# ManitoBoardL3.net
KiCad netlist of a schematic drawn in EAGLE
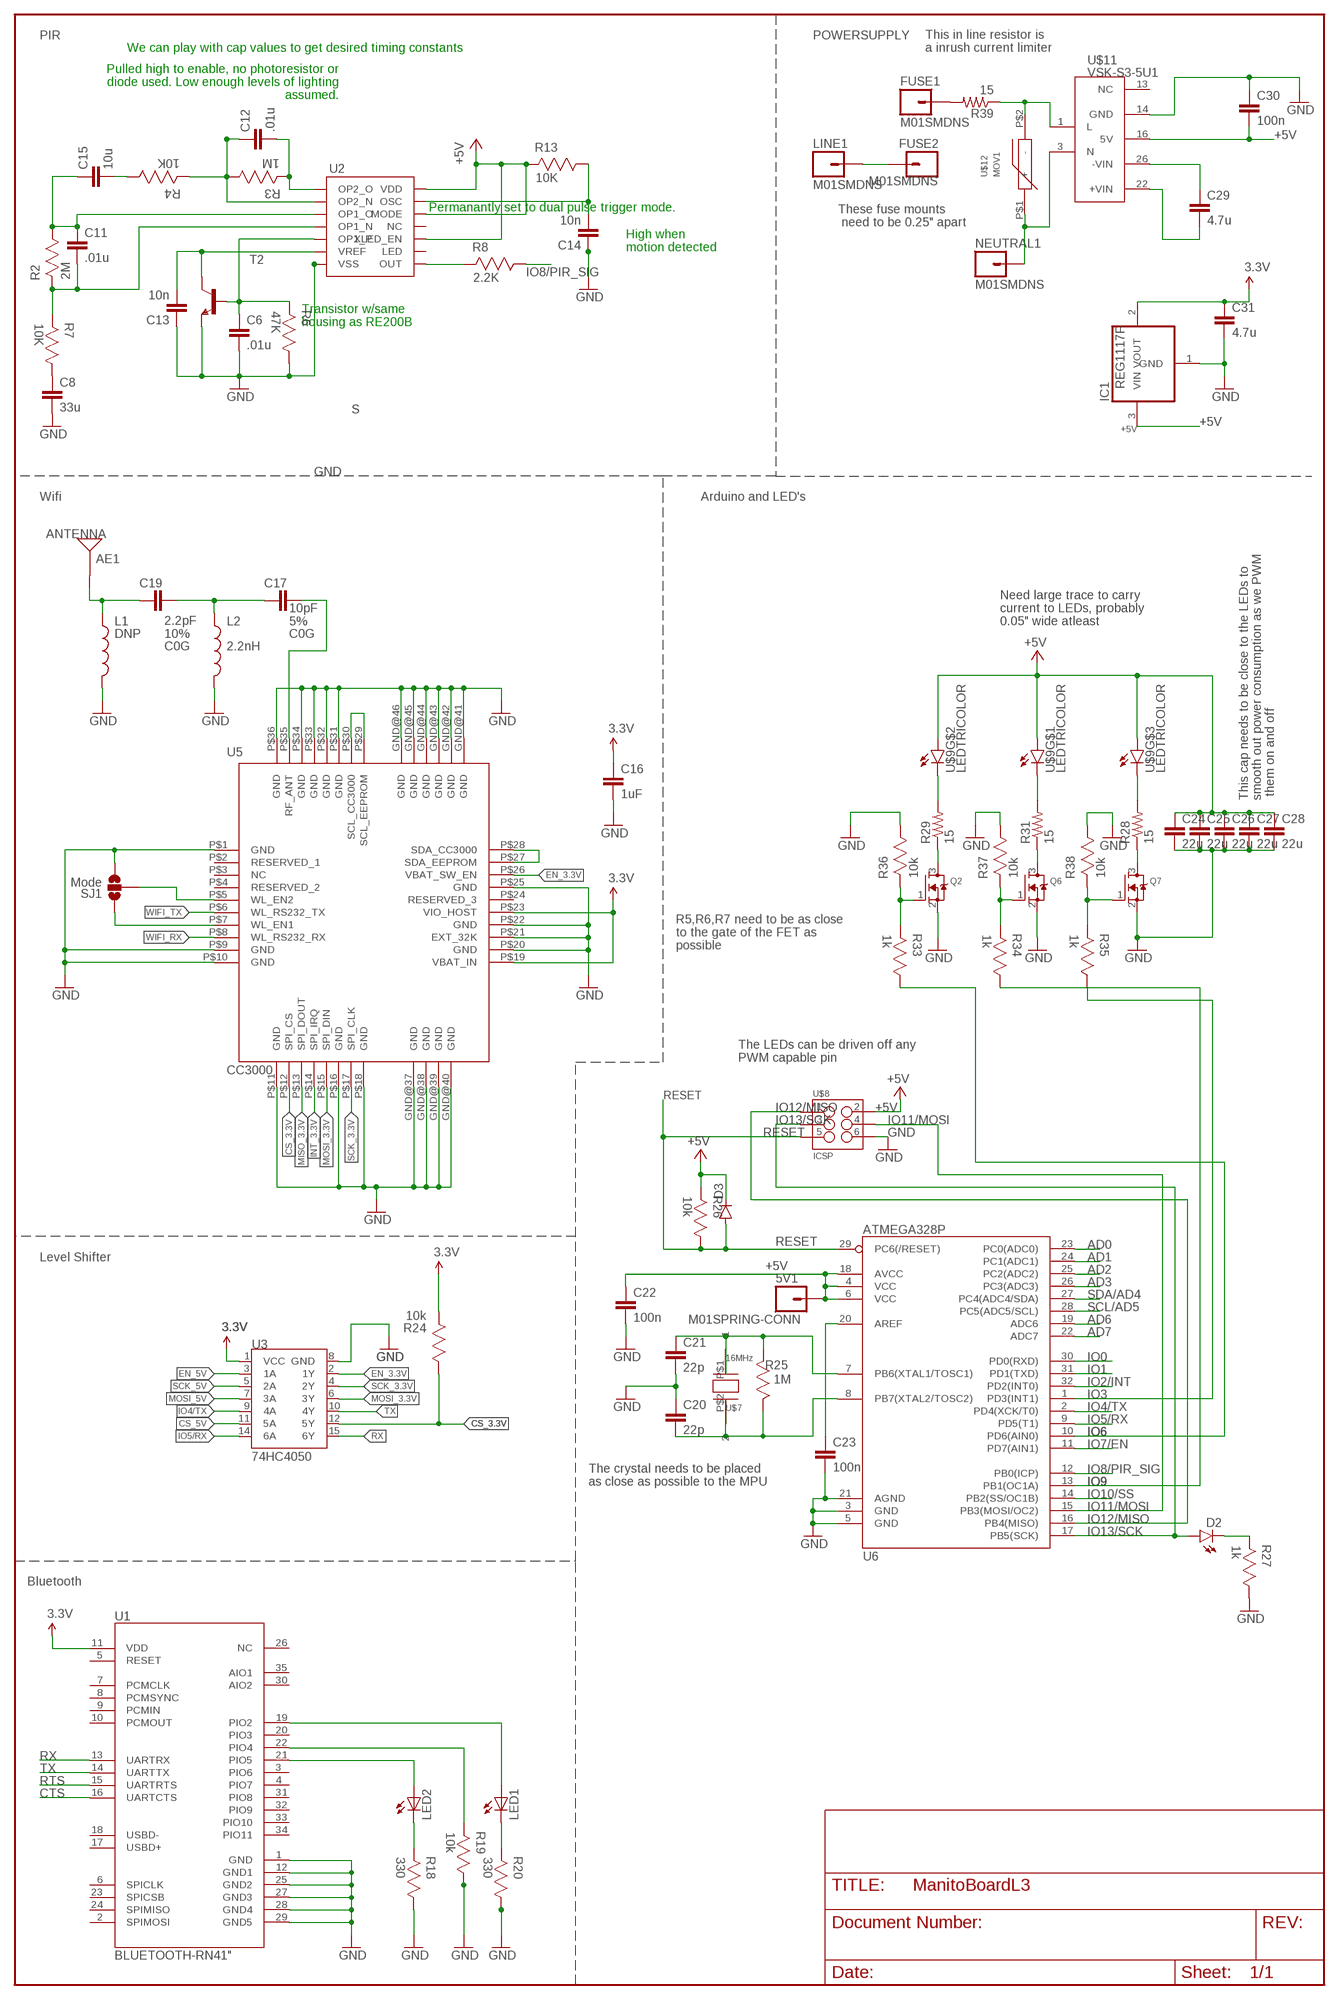
[diagram p0: schematic, sheet 1]

(export (version "E")
  (design (tool "Eeschema 10.0.6"))
  (components
    (comp (ref "5V1")
      (value "M01SPRING-CONN")
      (footprint "eagle-import:SPRING-CONNECTOR")
      (libsource (lib "eagle-import") (part "M01SPRING-CONN"))
    )
    (comp (ref "AE1")
      (value "ANTENNA")
      (footprint "eagle-import:ANTENNA-CHIP_2500AT44M0400")
      (libsource (lib "eagle-import") (part "ANTENNA22500AT44M0400"))
    )
    (comp (ref "C6")
      (value ".01u")
      (footprint "eagle-import:0805")
      (libsource (lib "eagle-import") (part "CAP0805"))
    )
    (comp (ref "C8")
      (value "33u")
      (footprint "eagle-import:0805")
      (libsource (lib "eagle-import") (part "CAP0805"))
    )
    (comp (ref "C11")
      (value ".01u")
      (footprint "eagle-import:0805")
      (libsource (lib "eagle-import") (part "CAP0805"))
    )
    (comp (ref "C12")
      (value ".01u")
      (footprint "eagle-import:0805")
      (libsource (lib "eagle-import") (part "CAP0805"))
    )
    (comp (ref "C13")
      (value "10n")
      (footprint "eagle-import:0805")
      (libsource (lib "eagle-import") (part "CAP0805"))
    )
    (comp (ref "C14")
      (value "10n")
      (footprint "eagle-import:0805")
      (libsource (lib "eagle-import") (part "CAP0805"))
    )
    (comp (ref "C15")
      (value "10u")
      (footprint "eagle-import:0805")
      (libsource (lib "eagle-import") (part "CAP0805"))
    )
    (comp (ref "C16")
      (value "1uF")
      (footprint "eagle-import:0805")
      (libsource (lib "eagle-import") (part "SparkFun-Capacitors_CAP0805"))
    )
    (comp (ref "C17")
      (value "10pF")
      (footprint "eagle-import:0603-CAP")
      (fields (field (name "COEFF") "C0G") (field (name "TOL") "5%"))
      (libsource (lib "eagle-import") (part "SparkFun-Capacitors_CAP0603-CAP"))
    )
    (comp (ref "C19")
      (value "2.2pF")
      (footprint "eagle-import:0603-CAP")
      (fields (field (name "COEFF") "C0G") (field (name "TOL") "10%"))
      (libsource (lib "eagle-import") (part "SparkFun-Capacitors_CAP0603-CAP"))
    )
    (comp (ref "C20")
      (value "22p")
      (footprint "eagle-import:0603-CAP")
      (libsource (lib "eagle-import") (part "CAP0603-CAP"))
    )
    (comp (ref "C21")
      (value "22p")
      (footprint "eagle-import:0603-CAP")
      (libsource (lib "eagle-import") (part "CAP0603-CAP"))
    )
    (comp (ref "C22")
      (value "100n")
      (footprint "eagle-import:0603-CAP")
      (libsource (lib "eagle-import") (part "CAP0603-CAP"))
    )
    (comp (ref "C23")
      (value "100n")
      (footprint "eagle-import:0603-CAP")
      (libsource (lib "eagle-import") (part "CAP0603-CAP"))
    )
    (comp (ref "C24")
      (value "22u")
      (footprint "eagle-import:0603-CAP")
      (libsource (lib "eagle-import") (part "CAP0603-CAP"))
    )
    (comp (ref "C25")
      (value "22u")
      (footprint "eagle-import:0603-CAP")
      (libsource (lib "eagle-import") (part "CAP0603-CAP"))
    )
    (comp (ref "C26")
      (value "22u")
      (footprint "eagle-import:0603-CAP")
      (libsource (lib "eagle-import") (part "CAP0603-CAP"))
    )
    (comp (ref "C27")
      (value "22u")
      (footprint "eagle-import:0603-CAP")
      (libsource (lib "eagle-import") (part "CAP0603-CAP"))
    )
    (comp (ref "C28")
      (value "22u")
      (footprint "eagle-import:0603-CAP")
      (libsource (lib "eagle-import") (part "CAP0603-CAP"))
    )
    (comp (ref "C29")
      (value "4.7u")
      (footprint "eagle-import:AXIAL-5MM")
      (libsource (lib "eagle-import") (part "CAP_"))
    )
    (comp (ref "C30")
      (value "100n")
      (footprint "eagle-import:0603-CAP")
      (libsource (lib "eagle-import") (part "CAP0603-CAP"))
    )
    (comp (ref "C31")
      (value "4.7u")
      (footprint "eagle-import:0603-CAP")
      (libsource (lib "eagle-import") (part "CAP0603-CAP"))
    )
    (comp (ref "D2")
      (value "LED-YELLOW0603")
      (footprint "eagle-import:LED-0603")
      (libsource (lib "eagle-import") (part "LED-YELLOW0603"))
    )
    (comp (ref "D3")
      (value "DIODESOD123")
      (footprint "eagle-import:SOD-123")
      (libsource (lib "eagle-import") (part "DIODESOD123"))
    )
    (comp (ref "FUSE1")
      (value "M01SMDNS")
      (footprint "eagle-import:1X01NS")
      (libsource (lib "eagle-import") (part "M01SMDNS"))
    )
    (comp (ref "FUSE2")
      (value "M01SMDNS")
      (footprint "eagle-import:1X01NS")
      (libsource (lib "eagle-import") (part "M01SMDNS"))
    )
    (comp (ref "IC1")
      (value "REG1117F")
      (footprint "eagle-import:DD-3")
      (fields (field (name "MF") "TEXAS INSTRUMENTS") (field (name "MPN") "REG1117FAKTTT"))
      (libsource (lib "eagle-import") (part "REG1117F"))
    )
    (comp (ref "L1")
      (value "DNP")
      (footprint "eagle-import:0603")
      (libsource (lib "eagle-import") (part "INDUCTOR0603"))
    )
    (comp (ref "L2")
      (value "2.2nH")
      (footprint "eagle-import:0603")
      (libsource (lib "eagle-import") (part "INDUCTOR0603"))
    )
    (comp (ref "LED1")
      (value "LED_ESML0603")
      (footprint "eagle-import:LED_SML0603")
      (libsource (lib "eagle-import") (part "LED_ESML0603"))
    )
    (comp (ref "LED2")
      (value "LED_ESML0603")
      (footprint "eagle-import:LED_SML0603")
      (libsource (lib "eagle-import") (part "LED_ESML0603"))
    )
    (comp (ref "LINE1")
      (value "M01SMDNS")
      (footprint "eagle-import:1X01NS")
      (libsource (lib "eagle-import") (part "M01SMDNS"))
    )
    (comp (ref "NEUTRAL1")
      (value "M01SMDNS")
      (footprint "eagle-import:1X01NS")
      (libsource (lib "eagle-import") (part "M01SMDNS"))
    )
    (comp (ref "Q2")
      (value "MOSFET-NREFLOW")
      (footprint "eagle-import:SOT23")
      (libsource (lib "eagle-import") (part "MOSFET-NREFLOW"))
    )
    (comp (ref "Q6")
      (value "MOSFET-NREFLOW")
      (footprint "eagle-import:SOT23")
      (libsource (lib "eagle-import") (part "MOSFET-NREFLOW"))
    )
    (comp (ref "Q7")
      (value "MOSFET-NREFLOW")
      (footprint "eagle-import:SOT23")
      (libsource (lib "eagle-import") (part "MOSFET-NREFLOW"))
    )
    (comp (ref "R2")
      (value "2M")
      (footprint "eagle-import:0603RESISTOR")
      (fields (field (name "MPN") "CRCW06031K21FKEA") (field (name "TOLERANCE") "± 1.0 %"))
      (libsource (lib "eagle-import") (part "0603RESISTOR1"))
    )
    (comp (ref "R3")
      (value "1M")
      (footprint "eagle-import:0603RESISTOR")
      (fields (field (name "MPN") "CRCW06031K21FKEA") (field (name "TOLERANCE") "± 1.0 %"))
      (libsource (lib "eagle-import") (part "0603RESISTOR1"))
    )
    (comp (ref "R4")
      (value "10K")
      (footprint "eagle-import:0603RESISTOR")
      (fields (field (name "MPN") "CRCW06031K21FKEA") (field (name "TOLERANCE") "± 1.0 %"))
      (libsource (lib "eagle-import") (part "0603RESISTOR1"))
    )
    (comp (ref "R6")
      (value "47K")
      (footprint "eagle-import:0603RESISTOR")
      (fields (field (name "MPN") "CRCW06031K21FKEA") (field (name "TOLERANCE") "± 1.0 %"))
      (libsource (lib "eagle-import") (part "0603RESISTOR1"))
    )
    (comp (ref "R7")
      (value "10K")
      (footprint "eagle-import:0603RESISTOR")
      (fields (field (name "MPN") "CRCW06031K21FKEA") (field (name "TOLERANCE") "± 1.0 %"))
      (libsource (lib "eagle-import") (part "0603RESISTOR1"))
    )
    (comp (ref "R8")
      (value "2.2K")
      (footprint "eagle-import:0603RESISTOR")
      (fields (field (name "MPN") "CRCW06031K21FKEA") (field (name "TOLERANCE") "± 1.0 %"))
      (libsource (lib "eagle-import") (part "0603RESISTOR1"))
    )
    (comp (ref "R13")
      (value "10K")
      (footprint "eagle-import:0603RESISTOR")
      (fields (field (name "MPN") "CRCW06031K21FKEA") (field (name "TOLERANCE") "± 1.0 %"))
      (libsource (lib "eagle-import") (part "0603RESISTOR1"))
    )
    (comp (ref "R18")
      (value "330")
      (footprint "eagle-import:0603RESISTOR")
      (fields (field (name "MPN") "CRCW06031K21FKEA") (field (name "TOLERANCE") "± 1.0 %"))
      (libsource (lib "eagle-import") (part "0603RESISTOR1"))
    )
    (comp (ref "R19")
      (value "10k")
      (footprint "eagle-import:0603RESISTOR")
      (fields (field (name "MPN") "CRCW06031K21FKEA") (field (name "TOLERANCE") "± 1.0 %"))
      (libsource (lib "eagle-import") (part "0603RESISTOR1"))
    )
    (comp (ref "R20")
      (value "330")
      (footprint "eagle-import:0603RESISTOR")
      (fields (field (name "MPN") "CRCW06031K21FKEA") (field (name "TOLERANCE") "± 1.0 %"))
      (libsource (lib "eagle-import") (part "0603RESISTOR1"))
    )
    (comp (ref "R24")
      (value "10k")
      (footprint "eagle-import:0603RESISTOR")
      (fields (field (name "MPN") "CRCW06031K21FKEA") (field (name "TOLERANCE") "± 1.0 %"))
      (libsource (lib "eagle-import") (part "0603RESISTOR1"))
    )
    (comp (ref "R25")
      (value "1M")
      (footprint "eagle-import:0603RESISTOR")
      (fields (field (name "MPN") "CRCW06031K21FKEA") (field (name "TOLERANCE") "± 1.0 %"))
      (libsource (lib "eagle-import") (part "0603RESISTOR1"))
    )
    (comp (ref "R26")
      (value "10k")
      (footprint "eagle-import:0603RESISTOR")
      (fields (field (name "MPN") "CRCW06031K21FKEA") (field (name "TOLERANCE") "± 1.0 %"))
      (libsource (lib "eagle-import") (part "0603RESISTOR1"))
    )
    (comp (ref "R27")
      (value "1k")
      (footprint "eagle-import:0603RESISTOR")
      (fields (field (name "MPN") "CRCW06031K21FKEA") (field (name "TOLERANCE") "± 1.0 %"))
      (libsource (lib "eagle-import") (part "0603RESISTOR1"))
    )
    (comp (ref "R28")
      (value "15")
      (footprint "eagle-import:AXIAL-0.6")
      (libsource (lib "eagle-import") (part "RESISTORPTH-1W"))
    )
    (comp (ref "R29")
      (value "15")
      (footprint "eagle-import:AXIAL-0.6")
      (libsource (lib "eagle-import") (part "RESISTORPTH-1W"))
    )
    (comp (ref "R31")
      (value "15")
      (footprint "eagle-import:AXIAL-0.6")
      (libsource (lib "eagle-import") (part "RESISTORPTH-1W"))
    )
    (comp (ref "R33")
      (value "1k")
      (footprint "eagle-import:0603RESISTOR")
      (fields (field (name "MPN") "CRCW06031K21FKEA") (field (name "TOLERANCE") "± 1.0 %"))
      (libsource (lib "eagle-import") (part "0603RESISTOR1"))
    )
    (comp (ref "R34")
      (value "1k")
      (footprint "eagle-import:0603RESISTOR")
      (fields (field (name "MPN") "CRCW06031K21FKEA") (field (name "TOLERANCE") "± 1.0 %"))
      (libsource (lib "eagle-import") (part "0603RESISTOR1"))
    )
    (comp (ref "R35")
      (value "1k")
      (footprint "eagle-import:0603RESISTOR")
      (fields (field (name "MPN") "CRCW06031K21FKEA") (field (name "TOLERANCE") "± 1.0 %"))
      (libsource (lib "eagle-import") (part "0603RESISTOR1"))
    )
    (comp (ref "R36")
      (value "10k")
      (footprint "eagle-import:0603RESISTOR")
      (fields (field (name "MPN") "CRCW06031K21FKEA") (field (name "TOLERANCE") "± 1.0 %"))
      (libsource (lib "eagle-import") (part "0603RESISTOR1"))
    )
    (comp (ref "R37")
      (value "10k")
      (footprint "eagle-import:0603RESISTOR")
      (fields (field (name "MPN") "CRCW06031K21FKEA") (field (name "TOLERANCE") "± 1.0 %"))
      (libsource (lib "eagle-import") (part "0603RESISTOR1"))
    )
    (comp (ref "R38")
      (value "10k")
      (footprint "eagle-import:0603RESISTOR")
      (fields (field (name "MPN") "CRCW06031K21FKEA") (field (name "TOLERANCE") "± 1.0 %"))
      (libsource (lib "eagle-import") (part "0603RESISTOR1"))
    )
    (comp (ref "R39")
      (value "15")
      (footprint "eagle-import:AXIAL-0.6")
      (libsource (lib "eagle-import") (part "RESISTORPTH-1W"))
    )
    (comp (ref "SJ1")
      (value "Mode")
      (footprint "eagle-import:SJ_3_PASTE1&2")
      (libsource (lib "eagle-import") (part "SOLDERJUMPER_2WAYPASTE1&2"))
    )
    (comp (ref "T2")
      (value "-NPN-TO5")
      (footprint "eagle-import:TO5")
      (libsource (lib "eagle-import") (part "-NPN-TO5"))
    )
    (comp (ref "U$7")
      (value "16MHz")
      (footprint "eagle-import:SMDCRYSTAL")
      (libsource (lib "eagle-import") (part "SMDCRYSTAL"))
    )
    (comp (ref "U$8")
      (value "ICSP")
      (footprint "eagle-import:2X3-ICSP")
      (libsource (lib "eagle-import") (part "6PIN-ICSP"))
    )
    (comp (ref "U$9")
      (value "LEDTRICOLOR")
      (footprint "eagle-import:TRICOLORLED")
      (libsource (lib "eagle-import") (part "LEDTRICOLOR"))
    )
    (comp (ref "U$11")
      (value "VSK-S3-5U1")
      (footprint "eagle-import:VSK-S3-DCAC")
      (libsource (lib "eagle-import") (part "VSK-S3-5U1"))
    )
    (comp (ref "U$12")
      (value "MOV1")
      (footprint "eagle-import:MOV")
      (libsource (lib "eagle-import") (part "MOV1"))
    )
    (comp (ref "U1")
      (value "BLUETOOTH-RN41\"")
      (footprint "eagle-import:RN41")
      (libsource (lib "eagle-import") (part "BLUETOOTH-RN41{dblquote}"))
    )
    (comp (ref "U2")
      (value "NCS36000")
      (footprint "eagle-import:SO14")
      (libsource (lib "eagle-import") (part "NCS36000"))
    )
    (comp (ref "U3")
      (value "74HC4050")
      (footprint "eagle-import:SO016")
      (libsource (lib "eagle-import") (part "HEX_CONVERTER"))
    )
    (comp (ref "U5")
      (value "CC3000")
      (footprint "eagle-import:QFN-46_CC3000")
      (libsource (lib "eagle-import") (part "CC3000"))
    )
    (comp (ref "U6")
      (value "ATMEGA328P")
      (footprint "eagle-import:TQFP32-08")
      (libsource (lib "eagle-import") (part "ATMEGA328_SMT"))
    )
  )
  (nets
    (net (code "1") (name "+5V") (class "Default")
      (node (ref "5V1") (pin "P$2") (pinfunction "1_P$2") (pintype "passive"))
      (node (ref "C22") (pin "1") (pinfunction "1_1") (pintype "passive"))
      (node (ref "C24") (pin "1") (pinfunction "1_1") (pintype "passive"))
      (node (ref "C25") (pin "1") (pinfunction "1_1") (pintype "passive"))
      (node (ref "C26") (pin "1") (pinfunction "1_1") (pintype "passive"))
      (node (ref "C27") (pin "1") (pinfunction "1_1") (pintype "passive"))
      (node (ref "C28") (pin "1") (pinfunction "1_1") (pintype "passive"))
      (node (ref "C30") (pin "2") (pinfunction "2_2") (pintype "passive"))
      (node (ref "D3") (pin "C") (pinfunction "C_C") (pintype "passive"))
      (node (ref "IC1") (pin "3") (pinfunction "VIN_3") (pintype "input"))
      (node (ref "R13") (pin "2") (pinfunction "2_2") (pintype "passive"))
      (node (ref "R26") (pin "2") (pinfunction "2_2") (pintype "passive"))
      (node (ref "U$11") (pin "16") (pinfunction "5V_16") (pintype "bidirectional"))
      (node (ref "U$8") (pin "2") (pinfunction "+5V_2") (pintype "power_in"))
      (node (ref "U$9") (pin "A1") (pinfunction "A_A1") (pintype "passive"))
      (node (ref "U$9") (pin "A2") (pinfunction "A_A2") (pintype "passive"))
      (node (ref "U$9") (pin "A3") (pinfunction "A_A3") (pintype "passive"))
      (node (ref "U2") (pin "10") (pinfunction "XLED_EN_10") (pintype "bidirectional"))
      (node (ref "U2") (pin "12") (pinfunction "MODE_12") (pintype "bidirectional"))
      (node (ref "U2") (pin "14") (pinfunction "VDD_14") (pintype "power_in"))
      (node (ref "U6") (pin "18") (pinfunction "AVCC_18") (pintype "bidirectional"))
      (node (ref "U6") (pin "4") (pinfunction "VCC_4") (pintype "bidirectional"))
      (node (ref "U6") (pin "6") (pinfunction "VCC_6") (pintype "bidirectional"))
    )
    (net (code "2") (name "/AD0") (class "Default")
      (node (ref "U6") (pin "23") (pinfunction "PC0(ADC0)_23") (pintype "bidirectional"))
    )
    (net (code "3") (name "/AD1") (class "Default")
      (node (ref "U6") (pin "24") (pinfunction "PC1(ADC1)_24") (pintype "bidirectional"))
    )
    (net (code "4") (name "/AD2") (class "Default")
      (node (ref "U6") (pin "25") (pinfunction "PC2(ADC2)_25") (pintype "bidirectional"))
    )
    (net (code "5") (name "/AD3") (class "Default")
      (node (ref "U6") (pin "26") (pinfunction "PC3(ADC3)_26") (pintype "bidirectional"))
    )
    (net (code "6") (name "/AD6") (class "Default")
      (node (ref "U6") (pin "19") (pinfunction "ADC6_19") (pintype "bidirectional"))
    )
    (net (code "7") (name "/AD7") (class "Default")
      (node (ref "U6") (pin "22") (pinfunction "ADC7_22") (pintype "bidirectional"))
    )
    (net (code "8") (name "/CTS") (class "Default")
      (node (ref "U1") (pin "16") (pinfunction "UARTCTS_16") (pintype "bidirectional"))
    )
    (net (code "9") (name "/IO0") (class "Default")
      (node (ref "U6") (pin "30") (pinfunction "PD0(RXD)_30") (pintype "bidirectional"))
    )
    (net (code "10") (name "/IO1") (class "Default")
      (node (ref "U6") (pin "31") (pinfunction "PD1(TXD)_31") (pintype "bidirectional"))
    )
    (net (code "11") (name "/IO2{slash}INT") (class "Default")
      (node (ref "U6") (pin "32") (pinfunction "PD2(INT0)_32") (pintype "bidirectional"))
    )
    (net (code "12") (name "/IO3") (class "Default")
      (node (ref "R35") (pin "1") (pinfunction "1_1") (pintype "passive"))
      (node (ref "U6") (pin "1") (pinfunction "PD3(INT1)_1") (pintype "bidirectional"))
    )
    (net (code "13") (name "/IO6") (class "Default")
      (node (ref "R33") (pin "1") (pinfunction "1_1") (pintype "passive"))
      (node (ref "U6") (pin "10") (pinfunction "PD6(AIN0)_10") (pintype "bidirectional"))
    )
    (net (code "14") (name "/IO7{slash}EN") (class "Default")
      (node (ref "U6") (pin "11") (pinfunction "PD7(AIN1)_11") (pintype "bidirectional"))
    )
    (net (code "15") (name "/IO8{slash}PIR_SIG") (class "Default")
      (node (ref "R8") (pin "1") (pinfunction "1_1") (pintype "passive"))
      (node (ref "U6") (pin "12") (pinfunction "PB0(ICP)_12") (pintype "bidirectional"))
    )
    (net (code "16") (name "/IO9") (class "Default")
      (node (ref "R34") (pin "1") (pinfunction "1_1") (pintype "passive"))
      (node (ref "U6") (pin "13") (pinfunction "PB1(OC1A)_13") (pintype "bidirectional"))
    )
    (net (code "17") (name "/IO10{slash}SS") (class "Default")
      (node (ref "U6") (pin "14") (pinfunction "PB2(SS/OC1B)_14") (pintype "bidirectional"))
    )
    (net (code "18") (name "/IO11{slash}MOSI") (class "Default")
      (node (ref "U$8") (pin "4") (pinfunction "MOSI_4") (pintype "bidirectional"))
      (node (ref "U6") (pin "15") (pinfunction "PB3(MOSI/OC2)_15") (pintype "bidirectional"))
    )
    (net (code "19") (name "/IO12{slash}MISO") (class "Default")
      (node (ref "U$8") (pin "1") (pinfunction "MISO_1") (pintype "bidirectional"))
      (node (ref "U6") (pin "16") (pinfunction "PB4(MISO)_16") (pintype "bidirectional"))
    )
    (net (code "20") (name "/IO13{slash}SCK") (class "Default")
      (node (ref "D2") (pin "A") (pinfunction "A_A") (pintype "passive"))
      (node (ref "U$8") (pin "3") (pinfunction "SCK_3") (pintype "bidirectional"))
      (node (ref "U6") (pin "17") (pinfunction "PB5(SCK)_17") (pintype "bidirectional"))
    )
    (net (code "22") (name "/RESET") (class "Default")
      (node (ref "D3") (pin "A") (pinfunction "A_A") (pintype "passive"))
      (node (ref "R26") (pin "1") (pinfunction "1_1") (pintype "passive"))
      (node (ref "U$8") (pin "5") (pinfunction "RESET_5") (pintype "bidirectional"))
      (node (ref "U6") (pin "29") (pinfunction "PC6(/RESET)_29") (pintype "bidirectional"))
    )
    (net (code "23") (name "/RTS") (class "Default")
      (node (ref "U1") (pin "15") (pinfunction "UARTRTS_15") (pintype "bidirectional"))
    )
    (net (code "24") (name "/S") (class "Default")
      (node (ref "C6") (pin "1") (pinfunction "1_1") (pintype "passive"))
      (node (ref "R6") (pin "2") (pinfunction "2_2") (pintype "passive"))
      (node (ref "T2") (pin "2") (pinfunction "B_2") (pintype "passive"))
      (node (ref "U2") (pin "5") (pinfunction "OP1_P_5") (pintype "bidirectional"))
    )
    (net (code "25") (name "/SCL{slash}AD5") (class "Default")
      (node (ref "U6") (pin "28") (pinfunction "PC5(ADC5/SCL)_28") (pintype "bidirectional"))
    )
    (net (code "26") (name "/SDA{slash}AD4") (class "Default")
      (node (ref "U6") (pin "27") (pinfunction "PC4(ADC4/SDA)_27") (pintype "bidirectional"))
    )
    (net (code "27") (name "3.3V") (class "Default")
      (node (ref "C16") (pin "1") (pinfunction "1_1") (pintype "passive"))
      (node (ref "C31") (pin "1") (pinfunction "1_1") (pintype "passive"))
      (node (ref "IC1") (pin "2") (pinfunction "VOUT_2") (pintype "output"))
      (node (ref "R24") (pin "2") (pinfunction "2_2") (pintype "passive"))
      (node (ref "U1") (pin "11") (pinfunction "VDD_11") (pintype "bidirectional"))
      (node (ref "U3") (pin "1") (pinfunction "VCC_1") (pintype "bidirectional"))
      (node (ref "U5") (pin "P$19") (pinfunction "VBAT_IN_P$19") (pintype "bidirectional"))
      (node (ref "U5") (pin "P$23") (pinfunction "VIO_HOST_P$23") (pintype "bidirectional"))
    )
    (net (code "28") (name "CS_3.3V") (class "Default")
      (node (ref "R24") (pin "1") (pinfunction "1_1") (pintype "passive"))
      (node (ref "U3") (pin "12") (pinfunction "5Y_12") (pintype "bidirectional"))
      (node (ref "U5") (pin "P$12") (pinfunction "SPI_CS_P$12") (pintype "bidirectional"))
    )
    (net (code "29") (name "CS_5V") (class "Default")
      (node (ref "U3") (pin "11") (pinfunction "5A_11") (pintype "bidirectional"))
    )
    (net (code "30") (name "EN_3.3V") (class "Default")
      (node (ref "U3") (pin "2") (pinfunction "1Y_2") (pintype "bidirectional"))
      (node (ref "U5") (pin "P$26") (pinfunction "VBAT_SW_EN_P$26") (pintype "bidirectional"))
    )
    (net (code "31") (name "EN_5V") (class "Default")
      (node (ref "U3") (pin "3") (pinfunction "1A_3") (pintype "bidirectional"))
    )
    (net (code "32") (name "GND") (class "Default")
      (node (ref "C13") (pin "1") (pinfunction "1_1") (pintype "passive"))
      (node (ref "C14") (pin "1") (pinfunction "1_1") (pintype "passive"))
      (node (ref "C16") (pin "2") (pinfunction "2_2") (pintype "passive"))
      (node (ref "C20") (pin "1") (pinfunction "1_1") (pintype "passive"))
      (node (ref "C21") (pin "2") (pinfunction "2_2") (pintype "passive"))
      (node (ref "C22") (pin "2") (pinfunction "2_2") (pintype "passive"))
      (node (ref "C23") (pin "2") (pinfunction "2_2") (pintype "passive"))
      (node (ref "C24") (pin "2") (pinfunction "2_2") (pintype "passive"))
      (node (ref "C25") (pin "2") (pinfunction "2_2") (pintype "passive"))
      (node (ref "C26") (pin "2") (pinfunction "2_2") (pintype "passive"))
      (node (ref "C27") (pin "2") (pinfunction "2_2") (pintype "passive"))
      (node (ref "C28") (pin "2") (pinfunction "2_2") (pintype "passive"))
      (node (ref "C30") (pin "1") (pinfunction "1_1") (pintype "passive"))
      (node (ref "C31") (pin "2") (pinfunction "2_2") (pintype "passive"))
      (node (ref "C6") (pin "2") (pinfunction "2_2") (pintype "passive"))
      (node (ref "C8") (pin "2") (pinfunction "2_2") (pintype "passive"))
      (node (ref "IC1") (pin "1") (pinfunction "GND_1") (pintype "power_in"))
      (node (ref "L1") (pin "2") (pinfunction "2_2") (pintype "passive"))
      (node (ref "L2") (pin "2") (pinfunction "2_2") (pintype "passive"))
      (node (ref "Q2") (pin "2") (pinfunction "S_2") (pintype "bidirectional"))
      (node (ref "Q6") (pin "2") (pinfunction "S_2") (pintype "bidirectional"))
      (node (ref "Q7") (pin "2") (pinfunction "S_2") (pintype "bidirectional"))
      (node (ref "R18") (pin "1") (pinfunction "1_1") (pintype "passive"))
      (node (ref "R19") (pin "1") (pinfunction "1_1") (pintype "passive"))
      (node (ref "R20") (pin "1") (pinfunction "1_1") (pintype "passive"))
      (node (ref "R27") (pin "1") (pinfunction "1_1") (pintype "passive"))
      (node (ref "R36") (pin "1") (pinfunction "1_1") (pintype "passive"))
      (node (ref "R37") (pin "1") (pinfunction "1_1") (pintype "passive"))
      (node (ref "R38") (pin "1") (pinfunction "1_1") (pintype "passive"))
      (node (ref "R6") (pin "1") (pinfunction "1_1") (pintype "passive"))
      (node (ref "SJ1") (pin "3") (pinfunction "3_3") (pintype "passive"))
      (node (ref "T2") (pin "1") (pinfunction "E_1") (pintype "passive"))
      (node (ref "U$11") (pin "14") (pinfunction "GND_14") (pintype "bidirectional"))
      (node (ref "U$8") (pin "6") (pinfunction "GND_6") (pintype "power_in"))
      (node (ref "U1") (pin "1") (pinfunction "GND_1") (pintype "bidirectional"))
      (node (ref "U1") (pin "12") (pinfunction "GND1_12") (pintype "bidirectional"))
      (node (ref "U1") (pin "25") (pinfunction "GND2_25") (pintype "bidirectional"))
      (node (ref "U1") (pin "27") (pinfunction "GND3_27") (pintype "bidirectional"))
      (node (ref "U1") (pin "28") (pinfunction "GND4_28") (pintype "bidirectional"))
      (node (ref "U1") (pin "29") (pinfunction "GND5_29") (pintype "bidirectional"))
      (node (ref "U2") (pin "7") (pinfunction "VSS_7") (pintype "power_in"))
      (node (ref "U3") (pin "8") (pinfunction "GND_8") (pintype "bidirectional"))
      (node (ref "U5") (pin "GND@37") (pinfunction "GND_GND@37") (pintype "bidirectional"))
      (node (ref "U5") (pin "GND@38") (pinfunction "GND_GND@38") (pintype "bidirectional"))
      (node (ref "U5") (pin "GND@39") (pinfunction "GND_GND@39") (pintype "bidirectional"))
      (node (ref "U5") (pin "GND@40") (pinfunction "GND_GND@40") (pintype "bidirectional"))
      (node (ref "U5") (pin "GND@41") (pinfunction "GND_GND@41") (pintype "bidirectional"))
      (node (ref "U5") (pin "GND@42") (pinfunction "GND_GND@42") (pintype "bidirectional"))
      (node (ref "U5") (pin "GND@43") (pinfunction "GND_GND@43") (pintype "bidirectional"))
      (node (ref "U5") (pin "GND@44") (pinfunction "GND_GND@44") (pintype "bidirectional"))
      (node (ref "U5") (pin "GND@45") (pinfunction "GND_GND@45") (pintype "bidirectional"))
      (node (ref "U5") (pin "GND@46") (pinfunction "GND_GND@46") (pintype "bidirectional"))
      (node (ref "U5") (pin "P$1") (pinfunction "GND_P$1") (pintype "bidirectional"))
      (node (ref "U5") (pin "P$10") (pinfunction "GND_P$10") (pintype "bidirectional"))
      (node (ref "U5") (pin "P$11") (pinfunction "GND_P$11") (pintype "bidirectional"))
      (node (ref "U5") (pin "P$16") (pinfunction "GND_P$16") (pintype "bidirectional"))
      (node (ref "U5") (pin "P$18") (pinfunction "GND_P$18") (pintype "bidirectional"))
      (node (ref "U5") (pin "P$20") (pinfunction "GND_P$20") (pintype "bidirectional"))
      (node (ref "U5") (pin "P$21") (pinfunction "EXT_32K_P$21") (pintype "bidirectional"))
      (node (ref "U5") (pin "P$22") (pinfunction "GND_P$22") (pintype "bidirectional"))
      (node (ref "U5") (pin "P$25") (pinfunction "GND_P$25") (pintype "bidirectional"))
      (node (ref "U5") (pin "P$31") (pinfunction "GND_P$31") (pintype "bidirectional"))
      (node (ref "U5") (pin "P$32") (pinfunction "GND_P$32") (pintype "bidirectional"))
      (node (ref "U5") (pin "P$33") (pinfunction "GND_P$33") (pintype "bidirectional"))
      (node (ref "U5") (pin "P$34") (pinfunction "GND_P$34") (pintype "bidirectional"))
      (node (ref "U5") (pin "P$36") (pinfunction "GND_P$36") (pintype "bidirectional"))
      (node (ref "U5") (pin "P$9") (pinfunction "GND_P$9") (pintype "bidirectional"))
      (node (ref "U6") (pin "21") (pinfunction "AGND_21") (pintype "bidirectional"))
      (node (ref "U6") (pin "3") (pinfunction "GND_3") (pintype "bidirectional"))
      (node (ref "U6") (pin "5") (pinfunction "GND_5") (pintype "bidirectional"))
    )
    (net (code "33") (name "INT_3.3V") (class "Default")
      (node (ref "U5") (pin "P$14") (pinfunction "SPI_IRQ_P$14") (pintype "bidirectional"))
    )
    (net (code "34") (name "IO4{slash}TX") (class "Default")
      (node (ref "U3") (pin "9") (pinfunction "4A_9") (pintype "bidirectional"))
      (node (ref "U6") (pin "2") (pinfunction "PD4(XCK/T0)_2") (pintype "bidirectional"))
    )
    (net (code "35") (name "IO5{slash}RX") (class "Default")
      (node (ref "U3") (pin "14") (pinfunction "6A_14") (pintype "bidirectional"))
      (node (ref "U6") (pin "9") (pinfunction "PD5(T1)_9") (pintype "bidirectional"))
    )
    (net (code "36") (name "MISO_3.3V") (class "Default")
      (node (ref "U5") (pin "P$13") (pinfunction "SPI_DOUT_P$13") (pintype "bidirectional"))
    )
    (net (code "37") (name "MOSI_3.3V") (class "Default")
      (node (ref "U3") (pin "6") (pinfunction "3Y_6") (pintype "bidirectional"))
      (node (ref "U5") (pin "P$15") (pinfunction "SPI_DIN_P$15") (pintype "bidirectional"))
    )
    (net (code "38") (name "MOSI_5V") (class "Default")
      (node (ref "U3") (pin "7") (pinfunction "3A_7") (pintype "bidirectional"))
    )
    (net (code "39") (name "Net-(AE1-SIGNAL)") (class "Default")
      (node (ref "AE1") (pin "FEED") (pinfunction "SIGNAL_FEED") (pintype "bidirectional"))
      (node (ref "C19") (pin "1") (pinfunction "1_1") (pintype "passive"))
      (node (ref "L1") (pin "1") (pinfunction "1_1") (pintype "passive"))
    )
    (net (code "40") (name "Net-(C8-Pad1)") (class "Default")
      (node (ref "C8") (pin "1") (pinfunction "1_1") (pintype "passive"))
      (node (ref "R7") (pin "1") (pinfunction "1_1") (pintype "passive"))
    )
    (net (code "41") (name "Net-(C15-Pad2)") (class "Default")
      (node (ref "C15") (pin "2") (pinfunction "2_2") (pintype "passive"))
      (node (ref "R4") (pin "1") (pinfunction "1_1") (pintype "passive"))
    )
    (net (code "42") (name "Net-(C17-Pad1)") (class "Default")
      (node (ref "C17") (pin "1") (pinfunction "1_1") (pintype "passive"))
      (node (ref "C19") (pin "2") (pinfunction "2_2") (pintype "passive"))
      (node (ref "L2") (pin "1") (pinfunction "1_1") (pintype "passive"))
    )
    (net (code "43") (name "Net-(C29-1)") (class "Default")
      (node (ref "C29") (pin "P$1") (pinfunction "1_P$1") (pintype "passive"))
      (node (ref "U$11") (pin "26") (pinfunction "-VIN_26") (pintype "bidirectional"))
    )
    (net (code "44") (name "Net-(C29-2)") (class "Default")
      (node (ref "C29") (pin "P$2") (pinfunction "2_P$2") (pintype "passive"))
      (node (ref "U$11") (pin "22") (pinfunction "+VIN_22") (pintype "bidirectional"))
    )
    (net (code "45") (name "Net-(D2-PadC)") (class "Default")
      (node (ref "D2") (pin "C") (pinfunction "C_C") (pintype "passive"))
      (node (ref "R27") (pin "2") (pinfunction "2_2") (pintype "passive"))
    )
    (net (code "46") (name "Net-(FUSE2-Pad1)") (class "Default")
      (node (ref "FUSE2") (pin "1") (pinfunction "1_1") (pintype "passive"))
      (node (ref "LINE1") (pin "1") (pinfunction "1_1") (pintype "passive"))
    )
    (net (code "47") (name "Net-(LED1-PadC)") (class "Default")
      (node (ref "LED1") (pin "C") (pinfunction "C_C") (pintype "passive"))
      (node (ref "R20") (pin "2") (pinfunction "2_2") (pintype "passive"))
    )
    (net (code "48") (name "Net-(LED2-PadC)") (class "Default")
      (node (ref "LED2") (pin "C") (pinfunction "C_C") (pintype "passive"))
      (node (ref "R18") (pin "2") (pinfunction "2_2") (pintype "passive"))
    )
    (net (code "49") (name "Net-(Q2-D)") (class "Default")
      (node (ref "Q2") (pin "3") (pinfunction "D_3") (pintype "bidirectional"))
      (node (ref "R29") (pin "P$1") (pinfunction "1_P$1") (pintype "passive"))
    )
    (net (code "50") (name "Net-(Q2-G)") (class "Default")
      (node (ref "Q2") (pin "1") (pinfunction "G_1") (pintype "bidirectional"))
      (node (ref "R33") (pin "2") (pinfunction "2_2") (pintype "passive"))
      (node (ref "R36") (pin "2") (pinfunction "2_2") (pintype "passive"))
    )
    (net (code "51") (name "Net-(Q6-D)") (class "Default")
      (node (ref "Q6") (pin "3") (pinfunction "D_3") (pintype "bidirectional"))
      (node (ref "R31") (pin "P$1") (pinfunction "1_P$1") (pintype "passive"))
    )
    (net (code "52") (name "Net-(Q6-G)") (class "Default")
      (node (ref "Q6") (pin "1") (pinfunction "G_1") (pintype "bidirectional"))
      (node (ref "R34") (pin "2") (pinfunction "2_2") (pintype "passive"))
      (node (ref "R37") (pin "2") (pinfunction "2_2") (pintype "passive"))
    )
    (net (code "53") (name "Net-(Q7-D)") (class "Default")
      (node (ref "Q7") (pin "3") (pinfunction "D_3") (pintype "bidirectional"))
      (node (ref "R28") (pin "P$1") (pinfunction "1_P$1") (pintype "passive"))
    )
    (net (code "54") (name "Net-(Q7-G)") (class "Default")
      (node (ref "Q7") (pin "1") (pinfunction "G_1") (pintype "bidirectional"))
      (node (ref "R35") (pin "2") (pinfunction "2_2") (pintype "passive"))
      (node (ref "R38") (pin "2") (pinfunction "2_2") (pintype "passive"))
    )
    (net (code "55") (name "Net-(R28-2)") (class "Default")
      (node (ref "R28") (pin "P$2") (pinfunction "2_P$2") (pintype "passive"))
      (node (ref "U$9") (pin "C3") (pinfunction "C_C3") (pintype "passive"))
    )
    (net (code "56") (name "Net-(R29-2)") (class "Default")
      (node (ref "R29") (pin "P$2") (pinfunction "2_P$2") (pintype "passive"))
      (node (ref "U$9") (pin "C2") (pinfunction "C_C2") (pintype "passive"))
    )
    (net (code "57") (name "Net-(R31-2)") (class "Default")
      (node (ref "R31") (pin "P$2") (pinfunction "2_P$2") (pintype "passive"))
      (node (ref "U$9") (pin "C1") (pinfunction "C_C1") (pintype "passive"))
    )
    (net (code "58") (name "Net-(R39-1)") (class "Default")
      (node (ref "R39") (pin "P$1") (pinfunction "1_P$1") (pintype "passive"))
      (node (ref "U$11") (pin "1") (pinfunction "L_1") (pintype "bidirectional"))
      (node (ref "U$12") (pin "P$2") (pinfunction "-_P$2") (pintype "bidirectional"))
    )
    (net (code "59") (name "Net-(R39-2)") (class "Default")
      (node (ref "FUSE1") (pin "1") (pinfunction "1_1") (pintype "passive"))
      (node (ref "R39") (pin "P$2") (pinfunction "2_P$2") (pintype "passive"))
    )
    (net (code "60") (name "Net-(T2-C)") (class "Default")
      (node (ref "C13") (pin "2") (pinfunction "2_2") (pintype "passive"))
      (node (ref "T2") (pin "3") (pinfunction "C_3") (pintype "passive"))
      (node (ref "U2") (pin "6") (pinfunction "VREF_6") (pintype "power_in"))
    )
    (net (code "61") (name "Net-(U$7-1)") (class "Default")
      (node (ref "C21") (pin "1") (pinfunction "1_1") (pintype "passive"))
      (node (ref "R25") (pin "2") (pinfunction "2_2") (pintype "passive"))
      (node (ref "U$7") (pin "P$1") (pinfunction "1_P$1") (pintype "bidirectional"))
      (node (ref "U6") (pin "7") (pinfunction "PB6(XTAL1/TOSC1)_7") (pintype "bidirectional"))
    )
    (net (code "62") (name "Net-(U$7-2)") (class "Default")
      (node (ref "C20") (pin "2") (pinfunction "2_2") (pintype "passive"))
      (node (ref "R25") (pin "1") (pinfunction "1_1") (pintype "passive"))
      (node (ref "U$7") (pin "P$2") (pinfunction "2_P$2") (pintype "bidirectional"))
      (node (ref "U6") (pin "8") (pinfunction "PB7(XTAL2/TOSC2)_8") (pintype "bidirectional"))
    )
    (net (code "63") (name "Net-(U$11-N)") (class "Default")
      (node (ref "NEUTRAL1") (pin "1") (pinfunction "1_1") (pintype "passive"))
      (node (ref "U$11") (pin "3") (pinfunction "N_3") (pintype "bidirectional"))
      (node (ref "U$12") (pin "P$1") (pinfunction "+_P$1") (pintype "bidirectional"))
    )
    (net (code "64") (name "Net-(U1-PIO2)") (class "Default")
      (node (ref "LED1") (pin "A") (pinfunction "A_A") (pintype "passive"))
      (node (ref "U1") (pin "19") (pinfunction "PIO2_19") (pintype "bidirectional"))
    )
    (net (code "65") (name "Net-(U1-PIO4)") (class "Default")
      (node (ref "R19") (pin "2") (pinfunction "2_2") (pintype "passive"))
      (node (ref "U1") (pin "22") (pinfunction "PIO4_22") (pintype "bidirectional"))
    )
    (net (code "66") (name "Net-(U1-PIO5)") (class "Default")
      (node (ref "LED2") (pin "A") (pinfunction "A_A") (pintype "passive"))
      (node (ref "U1") (pin "21") (pinfunction "PIO5_21") (pintype "bidirectional"))
    )
    (net (code "67") (name "Net-(U2-OP1_N)") (class "Default")
      (node (ref "C11") (pin "2") (pinfunction "2_2") (pintype "passive"))
      (node (ref "R2") (pin "2") (pinfunction "2_2") (pintype "passive"))
      (node (ref "R7") (pin "2") (pinfunction "2_2") (pintype "passive"))
      (node (ref "U2") (pin "4") (pinfunction "OP1_N_4") (pintype "bidirectional"))
    )
    (net (code "68") (name "Net-(U2-OP1_O)") (class "Default")
      (node (ref "C11") (pin "1") (pinfunction "1_1") (pintype "passive"))
      (node (ref "C15") (pin "1") (pinfunction "1_1") (pintype "passive"))
      (node (ref "R2") (pin "1") (pinfunction "1_1") (pintype "passive"))
      (node (ref "U2") (pin "3") (pinfunction "OP1_O_3") (pintype "bidirectional"))
    )
    (net (code "69") (name "Net-(U2-OP2_N)") (class "Default")
      (node (ref "C12") (pin "1") (pinfunction "1_1") (pintype "passive"))
      (node (ref "R3") (pin "1") (pinfunction "1_1") (pintype "passive"))
      (node (ref "R4") (pin "2") (pinfunction "2_2") (pintype "passive"))
      (node (ref "U2") (pin "2") (pinfunction "OP2_N_2") (pintype "bidirectional"))
    )
    (net (code "70") (name "Net-(U2-OP2_O)") (class "Default")
      (node (ref "C12") (pin "2") (pinfunction "2_2") (pintype "passive"))
      (node (ref "R3") (pin "2") (pinfunction "2_2") (pintype "passive"))
      (node (ref "U2") (pin "1") (pinfunction "OP2_O_1") (pintype "bidirectional"))
    )
    (net (code "71") (name "Net-(U2-OSC)") (class "Default")
      (node (ref "C14") (pin "2") (pinfunction "2_2") (pintype "passive"))
      (node (ref "R13") (pin "1") (pinfunction "1_1") (pintype "passive"))
      (node (ref "U2") (pin "13") (pinfunction "OSC_13") (pintype "bidirectional"))
    )
    (net (code "72") (name "Net-(U2-OUT)") (class "Default")
      (node (ref "R8") (pin "2") (pinfunction "2_2") (pintype "passive"))
      (node (ref "U2") (pin "8") (pinfunction "OUT_8") (pintype "bidirectional"))
    )
    (net (code "73") (name "Net-(U5-RF_ANT)") (class "Default")
      (node (ref "C17") (pin "2") (pinfunction "2_2") (pintype "passive"))
      (node (ref "U5") (pin "P$35") (pinfunction "RF_ANT_P$35") (pintype "bidirectional"))
    )
    (net (code "74") (name "Net-(U5-SCL_CC3000)") (class "Default")
      (node (ref "U5") (pin "P$29") (pinfunction "SCL_EEPROM_P$29") (pintype "bidirectional"))
      (node (ref "U5") (pin "P$30") (pinfunction "SCL_CC3000_P$30") (pintype "bidirectional"))
    )
    (net (code "75") (name "Net-(U5-SDA_CC3000)") (class "Default")
      (node (ref "U5") (pin "P$27") (pinfunction "SDA_EEPROM_P$27") (pintype "bidirectional"))
      (node (ref "U5") (pin "P$28") (pinfunction "SDA_CC3000_P$28") (pintype "bidirectional"))
    )
    (net (code "76") (name "Net-(U5-WL_EN1)") (class "Default")
      (node (ref "SJ1") (pin "1") (pinfunction "1_1") (pintype "passive"))
      (node (ref "U5") (pin "P$7") (pinfunction "WL_EN1_P$7") (pintype "bidirectional"))
    )
    (net (code "77") (name "Net-(U5-WL_EN2)") (class "Default")
      (node (ref "SJ1") (pin "2") (pinfunction "2_2") (pintype "passive"))
      (node (ref "U5") (pin "P$5") (pinfunction "WL_EN2_P$5") (pintype "bidirectional"))
    )
    (net (code "78") (name "Net-(U6-AREF)") (class "Default")
      (node (ref "C23") (pin "1") (pinfunction "1_1") (pintype "passive"))
      (node (ref "U6") (pin "20") (pinfunction "AREF_20") (pintype "bidirectional"))
    )
    (net (code "79") (name "RX") (class "Default")
      (node (ref "U1") (pin "13") (pinfunction "UARTRX_13") (pintype "bidirectional"))
      (node (ref "U3") (pin "15") (pinfunction "6Y_15") (pintype "bidirectional"))
    )
    (net (code "80") (name "SCK_3.3V") (class "Default")
      (node (ref "U3") (pin "4") (pinfunction "2Y_4") (pintype "bidirectional"))
      (node (ref "U5") (pin "P$17") (pinfunction "SPI_CLK_P$17") (pintype "bidirectional"))
    )
    (net (code "81") (name "SCK_5V") (class "Default")
      (node (ref "U3") (pin "5") (pinfunction "2A_5") (pintype "bidirectional"))
    )
    (net (code "82") (name "TX") (class "Default")
      (node (ref "U1") (pin "14") (pinfunction "UARTTX_14") (pintype "bidirectional"))
      (node (ref "U3") (pin "10") (pinfunction "4Y_10") (pintype "bidirectional"))
    )
    (net (code "83") (name "WIFI_RX") (class "Default")
      (node (ref "U5") (pin "P$8") (pinfunction "WL_RS232_RX_P$8") (pintype "bidirectional"))
    )
    (net (code "84") (name "WIFI_TX") (class "Default")
      (node (ref "U5") (pin "P$6") (pinfunction "WL_RS232_TX_P$6") (pintype "bidirectional"))
    )
    (net (code "85") (name "unconnected-(U$11-NC-Pad13)") (class "Default")
      (node (ref "U$11") (pin "13") (pinfunction "NC_13") (pintype "no_connect"))
    )
    (net (code "86") (name "unconnected-(U1-AIO1-Pad35)") (class "Default")
      (node (ref "U1") (pin "35") (pinfunction "AIO1_35") (pintype "bidirectional"))
    )
    (net (code "87") (name "unconnected-(U1-AIO2-Pad30)") (class "Default")
      (node (ref "U1") (pin "30") (pinfunction "AIO2_30") (pintype "bidirectional"))
    )
    (net (code "88") (name "unconnected-(U1-NC-Pad26)") (class "Default")
      (node (ref "U1") (pin "26") (pinfunction "NC_26") (pintype "bidirectional"))
    )
    (net (code "89") (name "unconnected-(U1-PCMCLK-Pad7)") (class "Default")
      (node (ref "U1") (pin "7") (pinfunction "PCMCLK_7") (pintype "bidirectional"))
    )
    (net (code "90") (name "unconnected-(U1-PCMIN-Pad9)") (class "Default")
      (node (ref "U1") (pin "9") (pinfunction "PCMIN_9") (pintype "bidirectional"))
    )
    (net (code "91") (name "unconnected-(U1-PCMOUT-Pad10)") (class "Default")
      (node (ref "U1") (pin "10") (pinfunction "PCMOUT_10") (pintype "bidirectional"))
    )
    (net (code "92") (name "unconnected-(U1-PCMSYNC-Pad8)") (class "Default")
      (node (ref "U1") (pin "8") (pinfunction "PCMSYNC_8") (pintype "bidirectional"))
    )
    (net (code "93") (name "unconnected-(U1-PIO3-Pad20)") (class "Default")
      (node (ref "U1") (pin "20") (pinfunction "PIO3_20") (pintype "bidirectional"))
    )
    (net (code "94") (name "unconnected-(U1-PIO6-Pad3)") (class "Default")
      (node (ref "U1") (pin "3") (pinfunction "PIO6_3") (pintype "bidirectional"))
    )
    (net (code "95") (name "unconnected-(U1-PIO7-Pad4)") (class "Default")
      (node (ref "U1") (pin "4") (pinfunction "PIO7_4") (pintype "bidirectional"))
    )
    (net (code "96") (name "unconnected-(U1-PIO8-Pad31)") (class "Default")
      (node (ref "U1") (pin "31") (pinfunction "PIO8_31") (pintype "bidirectional"))
    )
    (net (code "97") (name "unconnected-(U1-PIO9-Pad32)") (class "Default")
      (node (ref "U1") (pin "32") (pinfunction "PIO9_32") (pintype "bidirectional"))
    )
    (net (code "98") (name "unconnected-(U1-PIO10-Pad33)") (class "Default")
      (node (ref "U1") (pin "33") (pinfunction "PIO10_33") (pintype "bidirectional"))
    )
    (net (code "99") (name "unconnected-(U1-PIO11-Pad34)") (class "Default")
      (node (ref "U1") (pin "34") (pinfunction "PIO11_34") (pintype "bidirectional"))
    )
    (net (code "100") (name "unconnected-(U1-RESET-Pad5)") (class "Default")
      (node (ref "U1") (pin "5") (pinfunction "RESET_5") (pintype "bidirectional"))
    )
    (net (code "101") (name "unconnected-(U1-SPICLK-Pad6)") (class "Default")
      (node (ref "U1") (pin "6") (pinfunction "SPICLK_6") (pintype "bidirectional"))
    )
    (net (code "102") (name "unconnected-(U1-SPICSB-Pad23)") (class "Default")
      (node (ref "U1") (pin "23") (pinfunction "SPICSB_23") (pintype "bidirectional"))
    )
    (net (code "103") (name "unconnected-(U1-SPIMISO-Pad24)") (class "Default")
      (node (ref "U1") (pin "24") (pinfunction "SPIMISO_24") (pintype "bidirectional"))
    )
    (net (code "104") (name "unconnected-(U1-SPIMOSI-Pad2)") (class "Default")
      (node (ref "U1") (pin "2") (pinfunction "SPIMOSI_2") (pintype "bidirectional"))
    )
    (net (code "105") (name "unconnected-(U1-USBD+-Pad17)") (class "Default")
      (node (ref "U1") (pin "17") (pinfunction "USBD+_17") (pintype "bidirectional"))
    )
    (net (code "106") (name "unconnected-(U1-USBD--Pad18)") (class "Default")
      (node (ref "U1") (pin "18") (pinfunction "USBD-_18") (pintype "bidirectional"))
    )
    (net (code "107") (name "unconnected-(U2-LED-Pad9)") (class "Default")
      (node (ref "U2") (pin "9") (pinfunction "LED_9") (pintype "bidirectional"))
    )
    (net (code "108") (name "unconnected-(U2-NC-Pad11)") (class "Default")
      (node (ref "U2") (pin "11") (pinfunction "NC_11") (pintype "bidirectional"))
    )
    (net (code "109") (name "unconnected-(U5-NC-PadP$3)") (class "Default")
      (node (ref "U5") (pin "P$3") (pinfunction "NC_P$3") (pintype "bidirectional"))
    )
    (net (code "110") (name "unconnected-(U5-RESERVED_1-PadP$2)") (class "Default")
      (node (ref "U5") (pin "P$2") (pinfunction "RESERVED_1_P$2") (pintype "bidirectional"))
    )
    (net (code "111") (name "unconnected-(U5-RESERVED_2-PadP$4)") (class "Default")
      (node (ref "U5") (pin "P$4") (pinfunction "RESERVED_2_P$4") (pintype "bidirectional"))
    )
    (net (code "112") (name "unconnected-(U5-RESERVED_3-PadP$24)") (class "Default")
      (node (ref "U5") (pin "P$24") (pinfunction "RESERVED_3_P$24") (pintype "bidirectional"))
    )
  )
)
